# pengaduk_pupuk.net
KiCad netlist of a schematic drawn in EAGLE
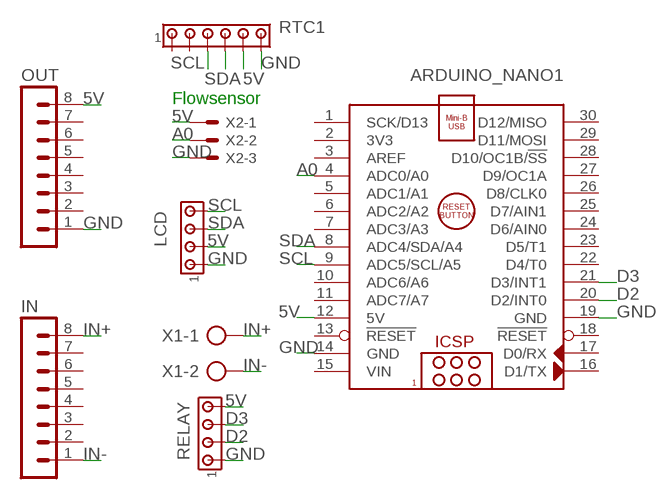
[diagram p0: schematic, sheet 1]

(export (version "E")
  (design (tool "Eeschema 10.0.6"))
  (components
    (comp (ref "ARDUINO_NANO1")
      (value "ARDUINO_NANO")
      (footprint "eagle-import:ARDUINO_NANO")
      (libsource (lib "eagle-import") (part "ARDUINO_NANO"))
    )
    (comp (ref "IN")
      (value "MA08-1")
      (footprint "eagle-import:MA08-1")
      (libsource (lib "eagle-import") (part "MA08-1"))
    )
    (comp (ref "LCD")
      (value "MTA04-100")
      (footprint "eagle-import:10X04MTA")
      (libsource (lib "eagle-import") (part "MTA04-100"))
    )
    (comp (ref "OUT")
      (value "MA08-1")
      (footprint "eagle-import:MA08-1")
      (libsource (lib "eagle-import") (part "MA08-1"))
    )
    (comp (ref "RELAY")
      (value "MTA04-100")
      (footprint "eagle-import:10X04MTA")
      (libsource (lib "eagle-import") (part "MTA04-100"))
    )
    (comp (ref "RTC1")
      (value "MTA06-100")
      (footprint "eagle-import:10X06MTA")
      (libsource (lib "eagle-import") (part "MTA06-100"))
    )
    (comp (ref "X1")
      (value "AK500/2-H")
      (footprint "eagle-import:AK500_2-H")
      (libsource (lib "eagle-import") (part "AK500/2-H"))
    )
    (comp (ref "X2")
      (value "KK-156-3")
      (footprint "eagle-import:KK-156-3")
      (fields (field (name "MF") "MOLEX"))
      (libsource (lib "eagle-import") (part "KK-156-3"))
    )
  )
  (nets
    (net (code "1") (name "/5V") (class "Default")
      (node (ref "ARDUINO_NANO1") (pin "12") (pinfunction "5V_12") (pintype "power_in"))
      (node (ref "LCD") (pin "2") (pinfunction "2_2") (pintype "passive"))
      (node (ref "OUT") (pin "8") (pinfunction "8_8") (pintype "passive"))
      (node (ref "RELAY") (pin "4") (pinfunction "4_4") (pintype "passive"))
      (node (ref "RTC1") (pin "5") (pinfunction "5_5") (pintype "passive"))
      (node (ref "X2") (pin "1") (pinfunction "S_1") (pintype "passive"))
    )
    (net (code "2") (name "/A0") (class "Default")
      (node (ref "ARDUINO_NANO1") (pin "4") (pinfunction "ADC0/A0_4") (pintype "bidirectional"))
      (node (ref "X2") (pin "2") (pinfunction "S_2") (pintype "passive"))
    )
    (net (code "3") (name "/D2") (class "Default")
      (node (ref "ARDUINO_NANO1") (pin "20") (pinfunction "D2/INT0_20") (pintype "bidirectional"))
      (node (ref "RELAY") (pin "2") (pinfunction "2_2") (pintype "passive"))
    )
    (net (code "4") (name "/D3") (class "Default")
      (node (ref "ARDUINO_NANO1") (pin "21") (pinfunction "D3/INT1_21") (pintype "bidirectional"))
      (node (ref "RELAY") (pin "3") (pinfunction "3_3") (pintype "passive"))
    )
    (net (code "5") (name "/GND") (class "Default")
      (node (ref "ARDUINO_NANO1") (pin "14") (pinfunction "GND_14") (pintype "power_in"))
      (node (ref "ARDUINO_NANO1") (pin "19") (pinfunction "GND_19") (pintype "power_in"))
      (node (ref "LCD") (pin "1") (pinfunction "1_1") (pintype "passive"))
      (node (ref "OUT") (pin "1") (pinfunction "1_1") (pintype "passive"))
      (node (ref "RELAY") (pin "1") (pinfunction "1_1") (pintype "passive"))
      (node (ref "RTC1") (pin "6") (pinfunction "6_6") (pintype "passive"))
      (node (ref "X2") (pin "3") (pinfunction "S_3") (pintype "passive"))
    )
    (net (code "6") (name "/IN+") (class "Default")
      (node (ref "IN") (pin "8") (pinfunction "8_8") (pintype "passive"))
      (node (ref "X1") (pin "1") (pinfunction "KL_1") (pintype "passive"))
    )
    (net (code "7") (name "/IN-") (class "Default")
      (node (ref "IN") (pin "1") (pinfunction "1_1") (pintype "passive"))
      (node (ref "X1") (pin "2") (pinfunction "KL_2") (pintype "passive"))
    )
    (net (code "8") (name "/SCL") (class "Default")
      (node (ref "ARDUINO_NANO1") (pin "9") (pinfunction "ADC5/SCL/A5_9") (pintype "bidirectional"))
      (node (ref "LCD") (pin "4") (pinfunction "4_4") (pintype "passive"))
      (node (ref "RTC1") (pin "3") (pinfunction "3_3") (pintype "passive"))
    )
    (net (code "9") (name "/SDA") (class "Default")
      (node (ref "ARDUINO_NANO1") (pin "8") (pinfunction "ADC4/SDA/A4_8") (pintype "bidirectional"))
      (node (ref "LCD") (pin "3") (pinfunction "3_3") (pintype "passive"))
      (node (ref "RTC1") (pin "4") (pinfunction "4_4") (pintype "passive"))
    )
    (net (code "10") (name "/VIN") (class "Default")
      (node (ref "ARDUINO_NANO1") (pin "15") (pinfunction "VIN_15") (pintype "power_in"))
    )
    (net (code "11") (name "unconnected-(ARDUINO_NANO1-3V3-Pad2)") (class "Default")
      (node (ref "ARDUINO_NANO1") (pin "2") (pinfunction "3V3_2") (pintype "output"))
    )
    (net (code "12") (name "unconnected-(ARDUINO_NANO1-ADC1{slash}A1-Pad5)") (class "Default")
      (node (ref "ARDUINO_NANO1") (pin "5") (pinfunction "ADC1/A1_5") (pintype "bidirectional"))
    )
    (net (code "13") (name "unconnected-(ARDUINO_NANO1-ADC2{slash}A2-Pad6)") (class "Default")
      (node (ref "ARDUINO_NANO1") (pin "6") (pinfunction "ADC2/A2_6") (pintype "bidirectional"))
    )
    (net (code "14") (name "unconnected-(ARDUINO_NANO1-ADC3{slash}A3-Pad7)") (class "Default")
      (node (ref "ARDUINO_NANO1") (pin "7") (pinfunction "ADC3/A3_7") (pintype "bidirectional"))
    )
    (net (code "15") (name "unconnected-(ARDUINO_NANO1-ADC6{slash}A6-Pad10)") (class "Default")
      (node (ref "ARDUINO_NANO1") (pin "10") (pinfunction "ADC6/A6_10") (pintype "bidirectional"))
    )
    (net (code "16") (name "unconnected-(ARDUINO_NANO1-ADC7{slash}A7-Pad11)") (class "Default")
      (node (ref "ARDUINO_NANO1") (pin "11") (pinfunction "ADC7/A7_11") (pintype "bidirectional"))
    )
    (net (code "17") (name "unconnected-(ARDUINO_NANO1-AREF-Pad3)") (class "Default")
      (node (ref "ARDUINO_NANO1") (pin "3") (pinfunction "AREF_3") (pintype "input"))
    )
    (net (code "18") (name "unconnected-(ARDUINO_NANO1-D0{slash}RX-Pad17)") (class "Default")
      (node (ref "ARDUINO_NANO1") (pin "17") (pinfunction "D0/RX_17") (pintype "bidirectional"))
    )
    (net (code "19") (name "unconnected-(ARDUINO_NANO1-D1{slash}TX-Pad16)") (class "Default")
      (node (ref "ARDUINO_NANO1") (pin "16") (pinfunction "D1/TX_16") (pintype "bidirectional"))
    )
    (net (code "20") (name "unconnected-(ARDUINO_NANO1-D4{slash}T0-Pad22)") (class "Default")
      (node (ref "ARDUINO_NANO1") (pin "22") (pinfunction "D4/T0_22") (pintype "bidirectional"))
    )
    (net (code "21") (name "unconnected-(ARDUINO_NANO1-D5{slash}T1-Pad23)") (class "Default")
      (node (ref "ARDUINO_NANO1") (pin "23") (pinfunction "D5/T1_23") (pintype "bidirectional"))
    )
    (net (code "22") (name "unconnected-(ARDUINO_NANO1-D6{slash}AIN0-Pad24)") (class "Default")
      (node (ref "ARDUINO_NANO1") (pin "24") (pinfunction "D6/AIN0_24") (pintype "bidirectional"))
    )
    (net (code "23") (name "unconnected-(ARDUINO_NANO1-D7{slash}AIN1-Pad25)") (class "Default")
      (node (ref "ARDUINO_NANO1") (pin "25") (pinfunction "D7/AIN1_25") (pintype "bidirectional"))
    )
    (net (code "24") (name "unconnected-(ARDUINO_NANO1-D8{slash}CLK0-Pad26)") (class "Default")
      (node (ref "ARDUINO_NANO1") (pin "26") (pinfunction "D8/CLK0_26") (pintype "bidirectional"))
    )
    (net (code "25") (name "unconnected-(ARDUINO_NANO1-D9{slash}OC1A-Pad27)") (class "Default")
      (node (ref "ARDUINO_NANO1") (pin "27") (pinfunction "D9/OC1A_27") (pintype "bidirectional"))
    )
    (net (code "26") (name "unconnected-(ARDUINO_NANO1-D10{slash}OC1B{slash}~{SS}-Pad28)") (class "Default")
      (node (ref "ARDUINO_NANO1") (pin "28") (pinfunction "D10/OC1B/~{SS}_28") (pintype "bidirectional"))
    )
    (net (code "27") (name "unconnected-(ARDUINO_NANO1-D11{slash}MOSI-Pad29)") (class "Default")
      (node (ref "ARDUINO_NANO1") (pin "29") (pinfunction "D11/MOSI_29") (pintype "bidirectional"))
    )
    (net (code "28") (name "unconnected-(ARDUINO_NANO1-D12{slash}MISO-Pad30)") (class "Default")
      (node (ref "ARDUINO_NANO1") (pin "30") (pinfunction "D12/MISO_30") (pintype "bidirectional"))
    )
    (net (code "29") (name "unconnected-(ARDUINO_NANO1-SCK{slash}D13-Pad1)") (class "Default")
      (node (ref "ARDUINO_NANO1") (pin "1") (pinfunction "SCK/D13_1") (pintype "bidirectional"))
    )
    (net (code "30") (name "unconnected-(ARDUINO_NANO1-~{RESET}-Pad13)") (class "Default")
      (node (ref "ARDUINO_NANO1") (pin "13") (pinfunction "~{RESET}_13") (pintype "input"))
    )
    (net (code "31") (name "unconnected-(ARDUINO_NANO1-~{RESET}-Pad18)") (class "Default")
      (node (ref "ARDUINO_NANO1") (pin "18") (pinfunction "~{RESET}_18") (pintype "input"))
    )
    (net (code "32") (name "unconnected-(IN-Pad2)") (class "Default")
      (node (ref "IN") (pin "2") (pinfunction "2_2") (pintype "passive"))
    )
    (net (code "33") (name "unconnected-(IN-Pad3)") (class "Default")
      (node (ref "IN") (pin "3") (pinfunction "3_3") (pintype "passive"))
    )
    (net (code "34") (name "unconnected-(IN-Pad4)") (class "Default")
      (node (ref "IN") (pin "4") (pinfunction "4_4") (pintype "passive"))
    )
    (net (code "35") (name "unconnected-(IN-Pad5)") (class "Default")
      (node (ref "IN") (pin "5") (pinfunction "5_5") (pintype "passive"))
    )
    (net (code "36") (name "unconnected-(IN-Pad6)") (class "Default")
      (node (ref "IN") (pin "6") (pinfunction "6_6") (pintype "passive"))
    )
    (net (code "37") (name "unconnected-(IN-Pad7)") (class "Default")
      (node (ref "IN") (pin "7") (pinfunction "7_7") (pintype "passive"))
    )
    (net (code "38") (name "unconnected-(OUT-Pad2)") (class "Default")
      (node (ref "OUT") (pin "2") (pinfunction "2_2") (pintype "passive"))
    )
    (net (code "39") (name "unconnected-(OUT-Pad3)") (class "Default")
      (node (ref "OUT") (pin "3") (pinfunction "3_3") (pintype "passive"))
    )
    (net (code "40") (name "unconnected-(OUT-Pad4)") (class "Default")
      (node (ref "OUT") (pin "4") (pinfunction "4_4") (pintype "passive"))
    )
    (net (code "41") (name "unconnected-(OUT-Pad5)") (class "Default")
      (node (ref "OUT") (pin "5") (pinfunction "5_5") (pintype "passive"))
    )
    (net (code "42") (name "unconnected-(OUT-Pad6)") (class "Default")
      (node (ref "OUT") (pin "6") (pinfunction "6_6") (pintype "passive"))
    )
    (net (code "43") (name "unconnected-(OUT-Pad7)") (class "Default")
      (node (ref "OUT") (pin "7") (pinfunction "7_7") (pintype "passive"))
    )
    (net (code "44") (name "unconnected-(RTC1-Pad1)") (class "Default")
      (node (ref "RTC1") (pin "1") (pinfunction "1_1") (pintype "passive"))
    )
    (net (code "45") (name "unconnected-(RTC1-Pad2)") (class "Default")
      (node (ref "RTC1") (pin "2") (pinfunction "2_2") (pintype "passive"))
    )
  )
)
